# 15P2D_EDA.net
KiCad netlist of a schematic drawn in EasyEDA Pro
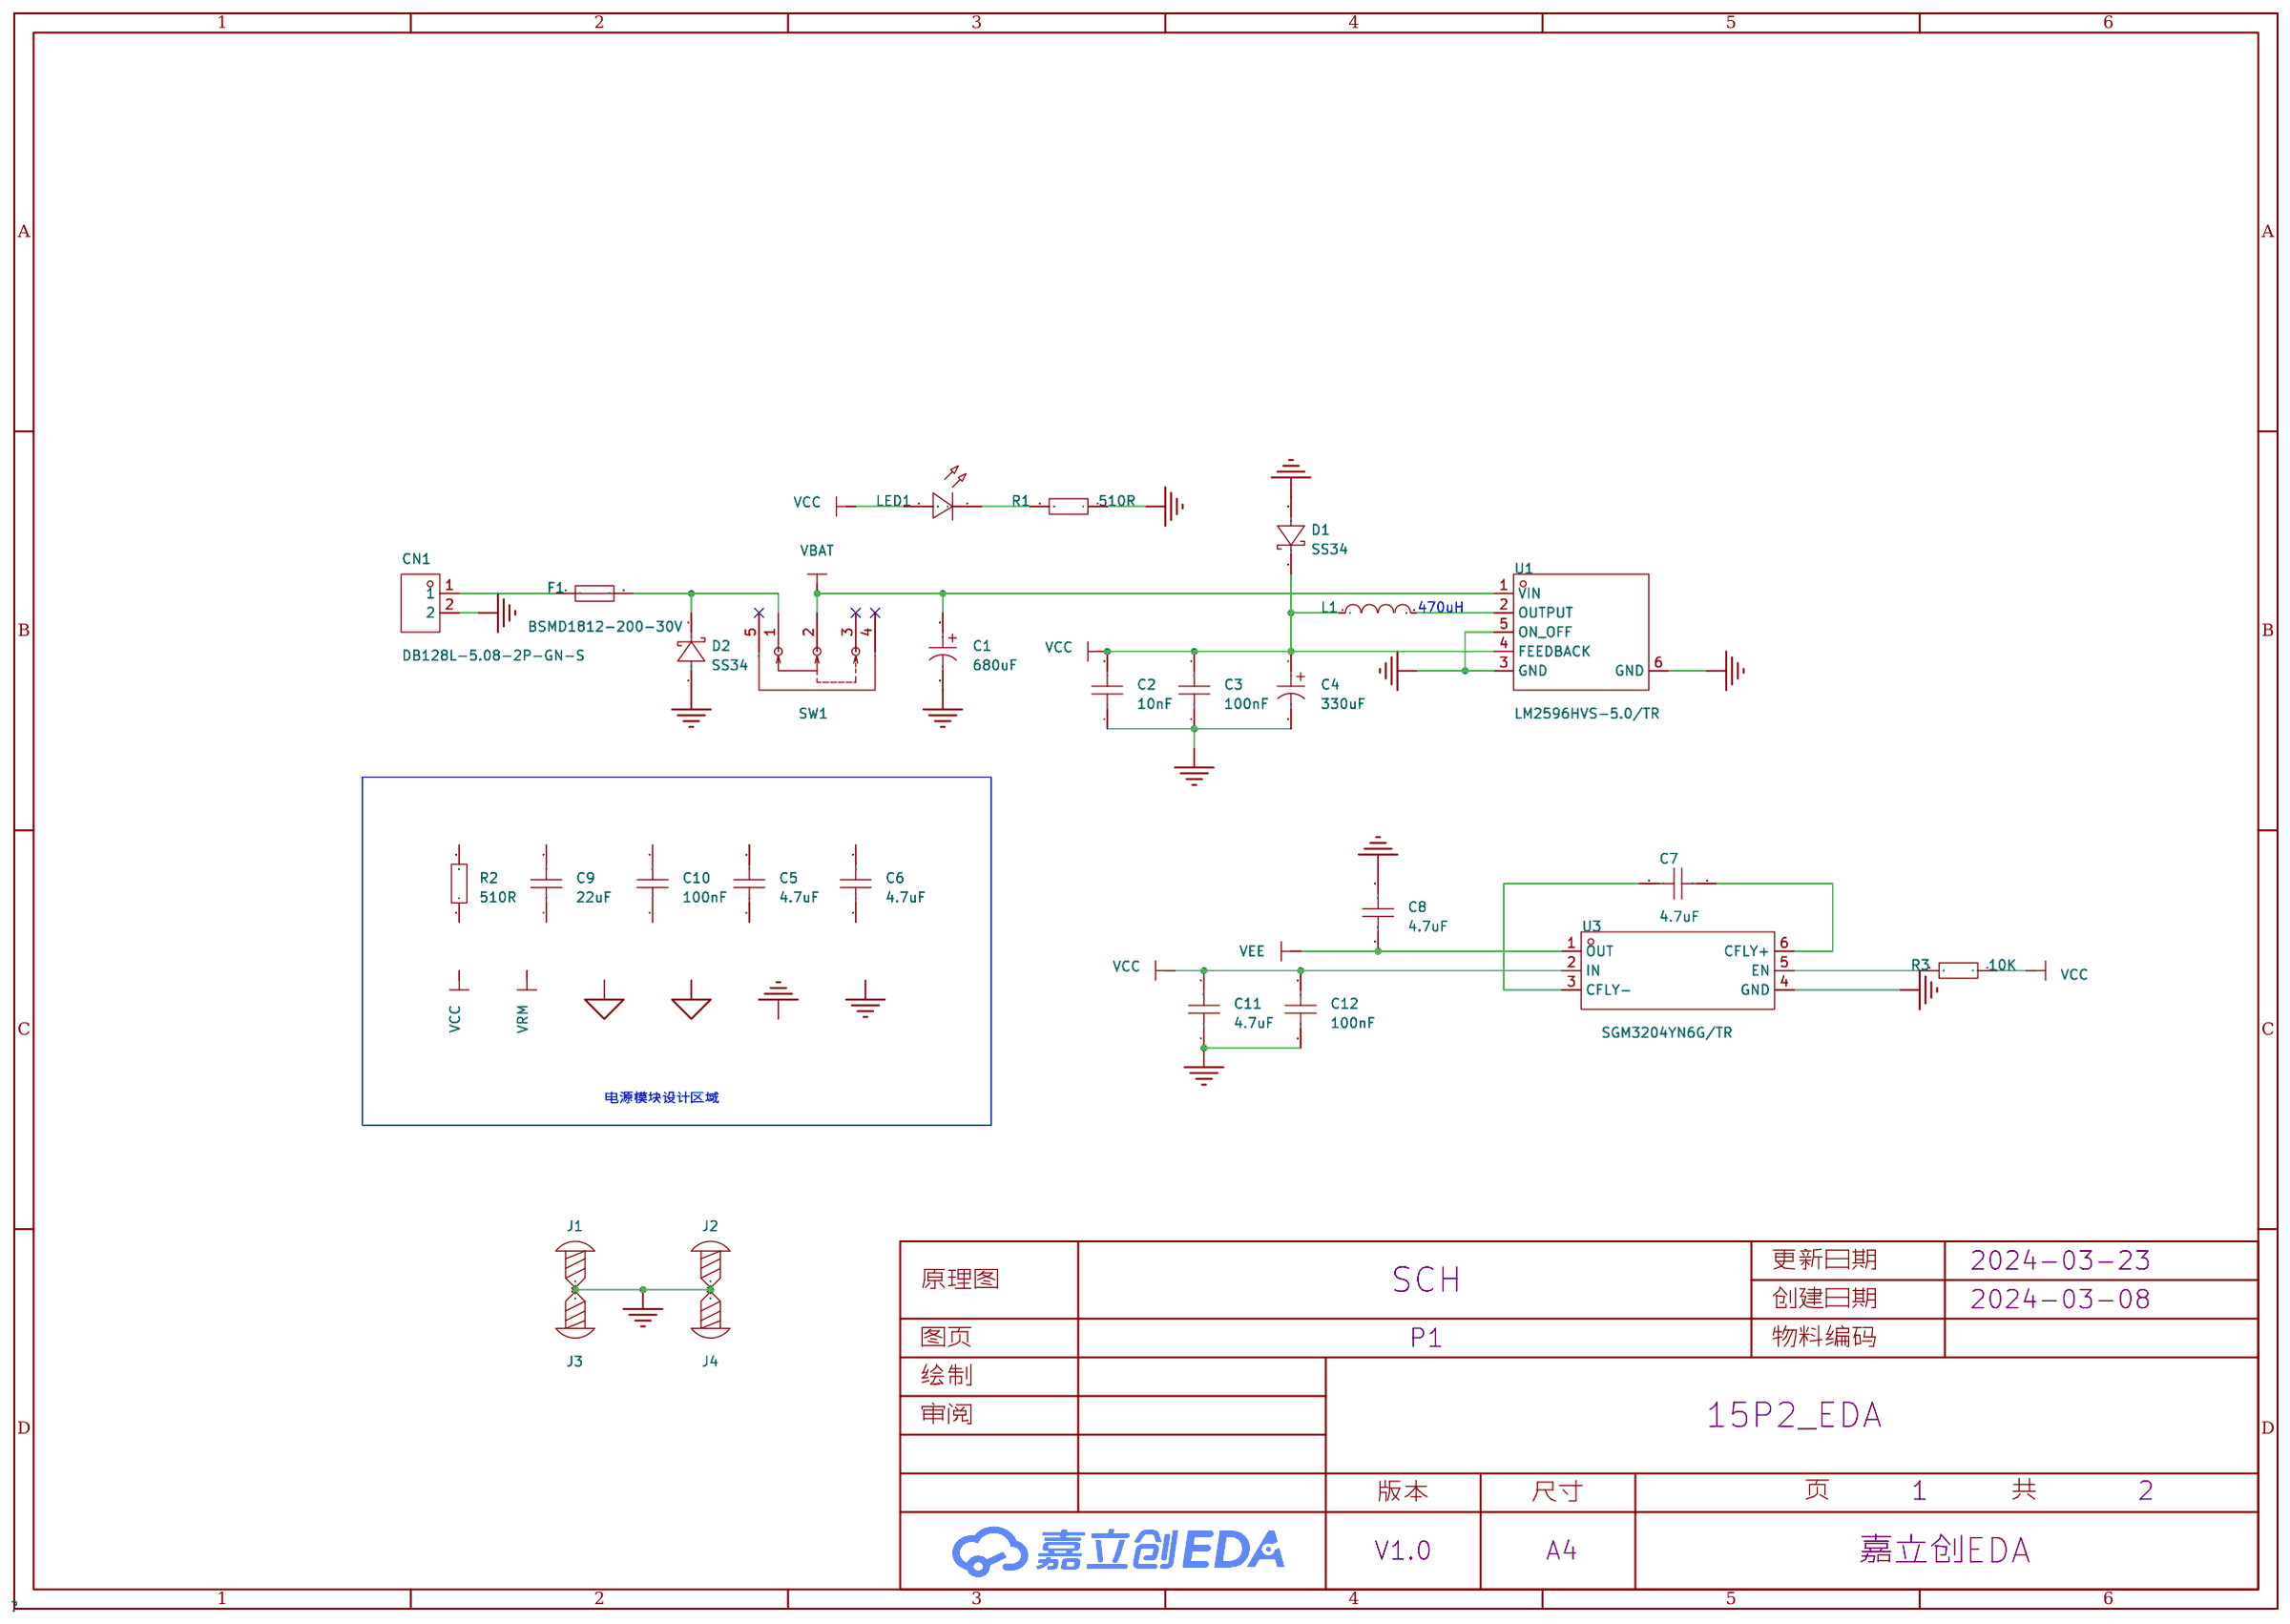
[diagram p0: P1]
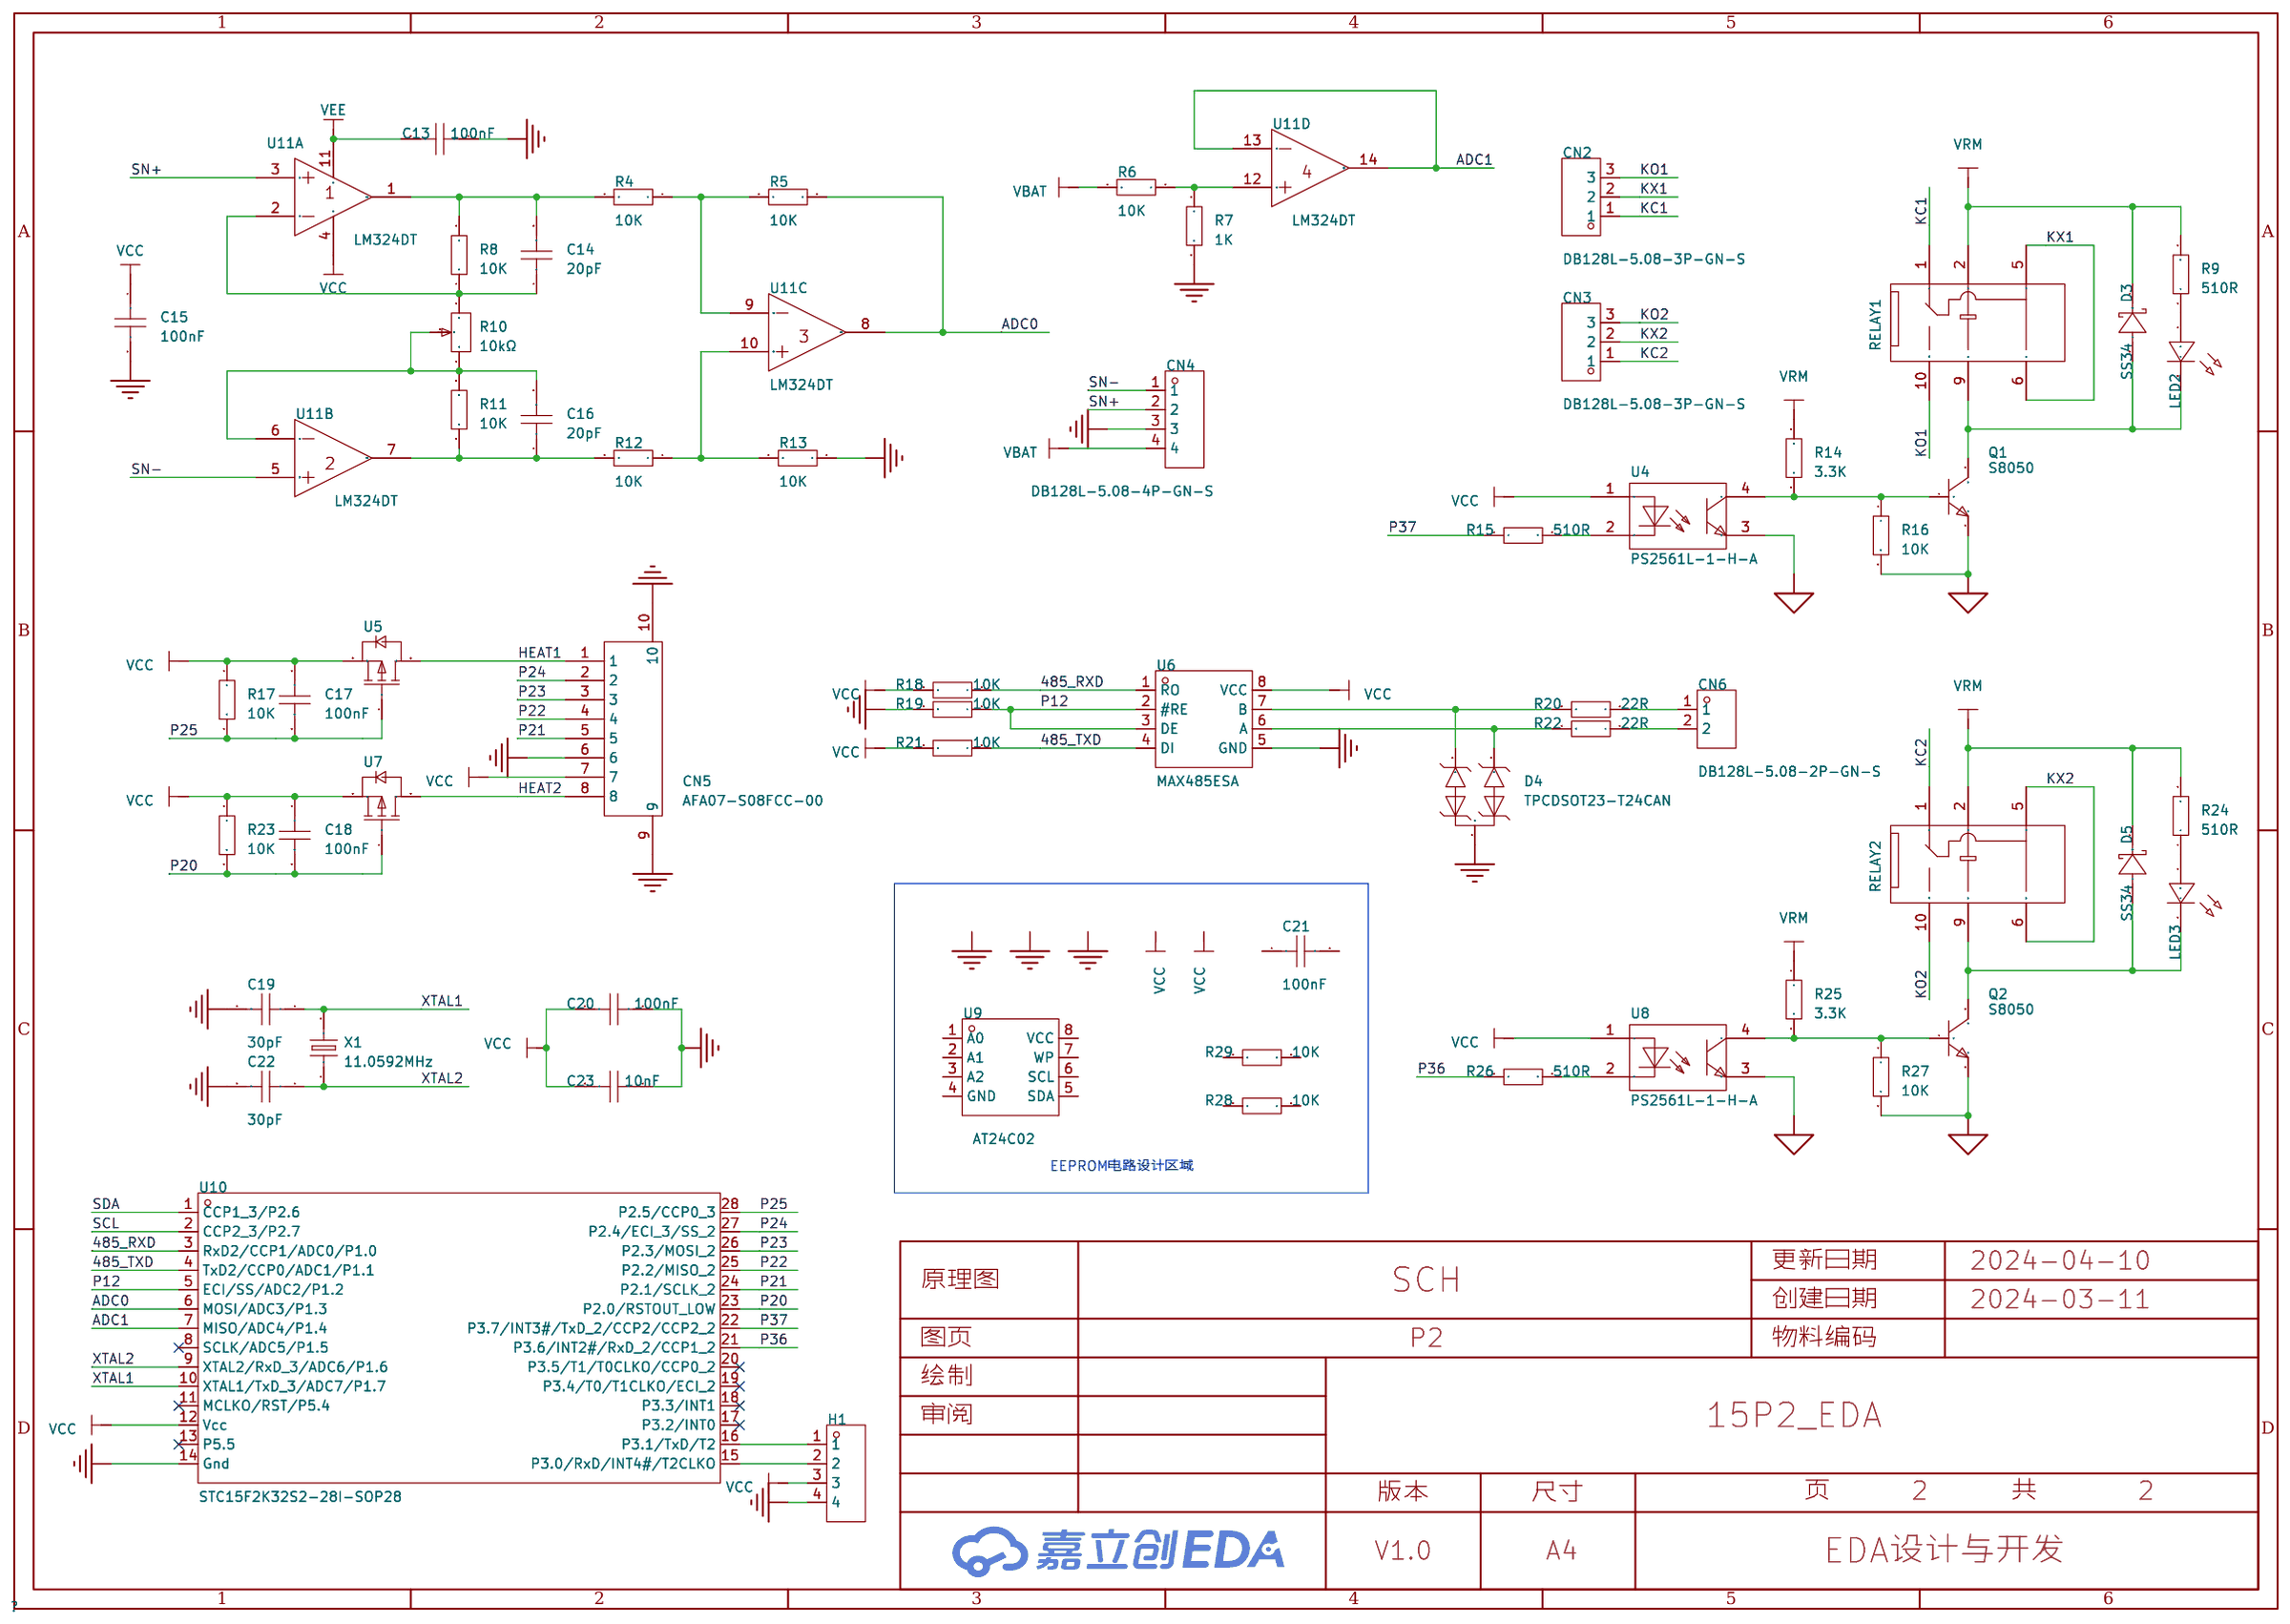
[diagram p1: P2]

(export (version "E")
  (design (tool "Eeschema 10.0.6"))
  (components
    (comp (ref "C1")
      (value "680uF")
      (footprint "easyedapro:CAP-SMD_BD10.0-L10.3-W10.3-LS11.3-FD")
      (description "容值:680uF;精度:±20%;额定电压:35V;纹波电流:380mA;")
      (fields (field (name "Manufacturer Part") "126RV0105") (field (name "Manufacturer") "KNSCHA(科尼盛)"))
      (libsource (lib "easyedapro") (part "126RV0105"))
    )
    (comp (ref "C2")
      (value "10nF")
      (footprint "easyedapro:C0805")
      (libsource (lib "easyedapro") (part "CapAcitance"))
    )
    (comp (ref "C3")
      (value "100nF")
      (footprint "easyedapro:C0805")
      (libsource (lib "easyedapro") (part "CapAcitance"))
    )
    (comp (ref "C4")
      (value "330uF")
      (footprint "easyedapro:CAP-SMD_BD6.3-L6.6-W6.6-LS7.6-RD")
      (description "容值:330uF;精度:±20%;额定电压:16V;纹波电流:170mA;")
      (fields (field (name "Manufacturer Part") "126RV0107") (field (name "Manufacturer") "KNSCHA(科尼盛)"))
      (libsource (lib "easyedapro") (part "126RV0107"))
    )
    (comp (ref "C5")
      (value "4.7uF")
      (footprint "easyedapro:C1206")
      (description "容值:22uF;精度:±10%;额定电压:16V;材质(温度系数):X5R;")
      (fields
        (field (name "Manufacturer Part") "CL31A226KOHNNNE")
        (field (name "Manufacturer") "SAMSUNG(三星)")
      )
      (libsource (lib "easyedapro") (part "CL31A226KOHNNNE"))
    )
    (comp (ref "C6")
      (value "4.7uF")
      (footprint "easyedapro:C1206")
      (description "容值:22uF;精度:±10%;额定电压:16V;材质(温度系数):X5R;")
      (fields
        (field (name "Manufacturer Part") "CL31A226KOHNNNE")
        (field (name "Manufacturer") "SAMSUNG(三星)")
      )
      (libsource (lib "easyedapro") (part "CL31A226KOHNNNE"))
    )
    (comp (ref "C7")
      (value "4.7uF")
      (footprint "easyedapro:C1206")
      (description "容值:22uF;精度:±10%;额定电压:16V;材质(温度系数):X5R;")
      (fields
        (field (name "Manufacturer Part") "CL31A226KOHNNNE")
        (field (name "Manufacturer") "SAMSUNG(三星)")
      )
      (libsource (lib "easyedapro") (part "CL31A226KOHNNNE"))
    )
    (comp (ref "C8")
      (value "4.7uF")
      (footprint "easyedapro:C1206")
      (description "容值:22uF;精度:±10%;额定电压:16V;材质(温度系数):X5R;")
      (fields
        (field (name "Manufacturer Part") "CL31A226KOHNNNE")
        (field (name "Manufacturer") "SAMSUNG(三星)")
      )
      (libsource (lib "easyedapro") (part "CL31A226KOHNNNE"))
    )
    (comp (ref "C9")
      (value "22uF")
      (footprint "easyedapro:C1206")
      (description "容值:22uF;精度:±10%;额定电压:16V;材质(温度系数):X5R;")
      (fields
        (field (name "Manufacturer Part") "CL31A226KOHNNNE")
        (field (name "Manufacturer") "SAMSUNG(三星)")
      )
      (libsource (lib "easyedapro") (part "CL31A226KOHNNNE"))
    )
    (comp (ref "C10")
      (value "100nF")
      (footprint "easyedapro:C0805")
      (libsource (lib "easyedapro") (part "CapAcitance"))
    )
    (comp (ref "C11")
      (value "4.7uF")
      (footprint "easyedapro:C1206")
      (description "容值:22uF;精度:±10%;额定电压:16V;材质(温度系数):X5R;")
      (fields
        (field (name "Manufacturer Part") "CL31A226KOHNNNE")
        (field (name "Manufacturer") "SAMSUNG(三星)")
      )
      (libsource (lib "easyedapro") (part "CL31A226KOHNNNE"))
    )
    (comp (ref "C12")
      (value "100nF")
      (footprint "easyedapro:C0805")
      (libsource (lib "easyedapro") (part "CapAcitance"))
    )
    (comp (ref "CN1")
      (value "DB128L-5.08-2P-GN-S")
      (footprint "easyedapro:CONN-TH_2P-P5.08_DB128L-5.08-2P")
      (fields (field (name "Manufacturer") "DORABO(地博电气)"))
      (libsource (lib "easyedapro") (part "DB128L-5.08-2P"))
    )
    (comp (ref "D1")
      (value "SS34")
      (footprint "easyedapro:SMA_L4.3-W2.5-LS5.0-RD")
      (description "二极管配置:独立式;正向压降(Vf):550mV@3A;直流反向耐压(Vr):40V;平均整流电流(Io):3A;")
      (fields (field (name "Manufacturer") "TWGMC(台湾迪嘉)"))
      (libsource (lib "easyedapro") (part "SS34_C727060"))
    )
    (comp (ref "D2")
      (value "SS34")
      (footprint "easyedapro:SMA_L4.3-W2.5-LS5.0-RD")
      (description "二极管配置:独立式;正向压降(Vf):550mV@3A;直流反向耐压(Vr):40V;平均整流电流(Io):3A;")
      (fields (field (name "Manufacturer") "TWGMC(台湾迪嘉)"))
      (libsource (lib "easyedapro") (part "SS34_C727060"))
    )
    (comp (ref "F1")
      (value "BSMD1812-200-30V")
      (footprint "easyedapro:F1812")
      (description "最大电压:30V;最大电流:40A;保持电流:2A;跳闸电流:4A;")
      (fields (field (name "Manufacturer") "BHFUSE(佰宏)"))
      (libsource (lib "easyedapro") (part "BSMD1812-200-30V"))
    )
    (comp (ref "J1") (value "~") (footprint "easyedapro:M2螺丝") (libsource (lib "easyedapro") (part "螺丝孔")))
    (comp (ref "J2") (value "~") (footprint "easyedapro:M2螺丝") (libsource (lib "easyedapro") (part "螺丝孔")))
    (comp (ref "J3") (value "~") (footprint "easyedapro:M2螺丝") (libsource (lib "easyedapro") (part "螺丝孔")))
    (comp (ref "J4") (value "~") (footprint "easyedapro:M2螺丝") (libsource (lib "easyedapro") (part "螺丝孔")))
    (comp (ref "L1")
      (value "470uH")
      (footprint "easyedapro:IND-SMD_L12.0-W12.0_YPRH120X")
      (description "电感值:470uH;精度:±20%;额定电流:1.06A;")
      (fields (field (name "Manufacturer Part") "YPRH1209-471M") (field (name "Manufacturer") "YJYCOIN(益嘉源)"))
      (libsource (lib "easyedapro") (part "YPRH1209-471M"))
    )
    (comp (ref "LED1")
      (value "~")
      (footprint "easyedapro:LED_TH-3mm")
      (libsource (lib "easyedapro") (part "LED_TH-R"))
    )
    (comp (ref "R1") (value "510R") (footprint "easyedapro:R0805") (libsource (lib "easyedapro") (part "电阻")))
    (comp (ref "R2") (value "510R") (footprint "easyedapro:R0805") (libsource (lib "easyedapro") (part "电阻")))
    (comp (ref "R3") (value "10K") (footprint "easyedapro:R0805") (libsource (lib "easyedapro") (part "电阻")))
    (comp (ref "SW1")
      (value "SK12D07VG4")
      (footprint "easyedapro:SW-TH_SK12D07VG4")
      (description "电路结构:单刀双掷;安装方式:侧插;额定电流(DC):500mA;额定电压(DC):50V;额定电流(AC):-;额定电压(AC):-;机械寿命:5千次;")
      (fields (field (name "Manufacturer") "SHOU HAN(首韩)"))
      (libsource (lib "easyedapro") (part "SK12D07VG4"))
    )
    (comp (ref "U1")
      (value "LM2596HVS-5.0/TR")
      (footprint "easyedapro:TO-263-5_L10.2-W8.9-P1.70-LS15.2-BR")
      (fields (field (name "Manufacturer") "HGSEMI(华冠)"))
      (libsource (lib "easyedapro") (part "LM2596HVS-5.0/TR"))
    )
    (comp (ref "U3")
      (value "SGM3204YN6G/TR")
      (footprint "easyedapro:SOT-23-6_L2.9-W1.6-P0.95-LS2.8-BR")
      (description "功能类型:-;输入电压:1.4V~5.5V;输出电压:-5.5V~-1.4V;输出电流(最大值):200mA;")
      (fields (field (name "Manufacturer") "SGMICRO(圣邦微)"))
      (libsource (lib "easyedapro") (part "SGM3204YN6G/TR"))
    )
    (comp (ref "C13")
      (value "100nF")
      (footprint "easyedapro:C0805")
      (libsource (lib "easyedapro") (part "CapAcitance"))
    )
    (comp (ref "C14")
      (value "20pF")
      (footprint "easyedapro:C0805")
      (libsource (lib "easyedapro") (part "CapAcitance"))
    )
    (comp (ref "C15")
      (value "100nF")
      (footprint "easyedapro:C0805")
      (libsource (lib "easyedapro") (part "CapAcitance"))
    )
    (comp (ref "C16")
      (value "20pF")
      (footprint "easyedapro:C0805")
      (libsource (lib "easyedapro") (part "CapAcitance"))
    )
    (comp (ref "C17")
      (value "100nF")
      (footprint "easyedapro:C0805")
      (libsource (lib "easyedapro") (part "CapAcitance"))
    )
    (comp (ref "C18")
      (value "100nF")
      (footprint "easyedapro:C0805")
      (libsource (lib "easyedapro") (part "CapAcitance"))
    )
    (comp (ref "C19")
      (value "30pF")
      (footprint "easyedapro:C0805")
      (libsource (lib "easyedapro") (part "CapAcitance"))
    )
    (comp (ref "C20")
      (value "100nF")
      (footprint "easyedapro:C0805")
      (libsource (lib "easyedapro") (part "CapAcitance"))
    )
    (comp (ref "C21")
      (value "100nF")
      (footprint "easyedapro:C0805")
      (libsource (lib "easyedapro") (part "CapAcitance"))
    )
    (comp (ref "C22")
      (value "30pF")
      (footprint "easyedapro:C0805")
      (libsource (lib "easyedapro") (part "CapAcitance"))
    )
    (comp (ref "C23")
      (value "10nF")
      (footprint "easyedapro:C0805")
      (libsource (lib "easyedapro") (part "CapAcitance"))
    )
    (comp (ref "CN2")
      (value "DB128L-5.08-3P-GN-S")
      (footprint "easyedapro:CONN-TH_DB128L-5.08-3P")
      (fields (field (name "Manufacturer") "DORABO(地博电气)"))
      (libsource (lib "easyedapro") (part "DB128L-5.08-3P"))
    )
    (comp (ref "CN3")
      (value "DB128L-5.08-3P-GN-S")
      (footprint "easyedapro:CONN-TH_DB128L-5.08-3P")
      (fields (field (name "Manufacturer") "DORABO(地博电气)"))
      (libsource (lib "easyedapro") (part "DB128L-5.08-3P"))
    )
    (comp (ref "CN4")
      (value "DB128L-5.08-4P-GN-S")
      (footprint "easyedapro:CONN-TH_4P_DB128L-5.08-4P-GN-S")
      (fields (field (name "Manufacturer") "DORABO(地博电气)"))
      (libsource (lib "easyedapro") (part "DB128L-5.08-4P-GN-S"))
    )
    (comp (ref "CN5")
      (value "AFA07-S08FCC-00")
      (footprint "easyedapro:FPC-SMD_P1.00-8P_LCS-XJ-H2.5")
      (description "锁定特性:抽屉式;触点类型:下接;触点数量:8P;间距:1mm;安装类型:卧贴;")
      (fields (field (name "Manufacturer") "JS(钜硕电子)"))
      (libsource (lib "easyedapro") (part "AFA07-S08FCC-00"))
    )
    (comp (ref "CN6")
      (value "DB128L-5.08-2P-GN-S")
      (footprint "easyedapro:CONN-TH_2P-P5.08_DB128L-5.08-2P")
      (fields (field (name "Manufacturer") "DORABO(地博电气)"))
      (libsource (lib "easyedapro") (part "DB128L-5.08-2P"))
    )
    (comp (ref "D3")
      (value "SS34")
      (footprint "easyedapro:SMA_L4.3-W2.5-LS5.0-RD")
      (description "二极管配置:独立式;正向压降(Vf):550mV@3A;直流反向耐压(Vr):40V;平均整流电流(Io):3A;")
      (fields (field (name "Manufacturer") "TWGMC(台湾迪嘉)"))
      (libsource (lib "easyedapro") (part "SS34_C727060"))
    )
    (comp (ref "D4")
      (value "TPCDSOT23-T24CAN")
      (footprint "easyedapro:SOT-23-3_L2.9-W1.3-P1.90-LS2.4-BR")
      (fields (field (name "Manufacturer") "TECH PUBLIC(台舟)"))
      (libsource (lib "easyedapro") (part "TPCDSOT23-T24CAN"))
    )
    (comp (ref "D5")
      (value "SS34")
      (footprint "easyedapro:SMA_L4.3-W2.5-LS5.0-RD")
      (description "二极管配置:独立式;正向压降(Vf):550mV@3A;直流反向耐压(Vr):40V;平均整流电流(Io):3A;")
      (fields (field (name "Manufacturer") "TWGMC(台湾迪嘉)"))
      (libsource (lib "easyedapro") (part "SS34_C727060"))
    )
    (comp (ref "H1")
      (value "~")
      (footprint "easyedapro:HDR-TH_4P-P2.54-V-F")
      (libsource (lib "easyedapro") (part "2.54-1*4P母"))
    )
    (comp (ref "LED2")
      (value "~")
      (footprint "easyedapro:LED_TH-3mm")
      (libsource (lib "easyedapro") (part "LED_TH-G"))
    )
    (comp (ref "LED3")
      (value "~")
      (footprint "easyedapro:LED_TH-3mm")
      (libsource (lib "easyedapro") (part "LED_TH-G"))
    )
    (comp (ref "Q1")
      (value "S8050")
      (footprint "easyedapro:SOT-23-3_L2.9-W1.3-P1.90-LS2.4-BR")
      (description "晶体管类型:NPN;集电极电流(Ic):500mA;集射极击穿电压(Vceo):25V;功率(Pd):300mW;")
      (fields (field (name "Manufacturer") "YONGYUTAI(永裕泰)"))
      (libsource (lib "easyedapro") (part "S8050_C2891804"))
    )
    (comp (ref "Q2")
      (value "S8050")
      (footprint "easyedapro:SOT-23-3_L2.9-W1.3-P1.90-LS2.4-BR")
      (description "晶体管类型:NPN;集电极电流(Ic):500mA;集射极击穿电压(Vceo):25V;功率(Pd):300mW;")
      (fields (field (name "Manufacturer") "YONGYUTAI(永裕泰)"))
      (libsource (lib "easyedapro") (part "S8050_C2891804"))
    )
    (comp (ref "R4") (value "10K") (footprint "easyedapro:R0805") (libsource (lib "easyedapro") (part "电阻")))
    (comp (ref "R5") (value "10K") (footprint "easyedapro:R0805") (libsource (lib "easyedapro") (part "电阻")))
    (comp (ref "R6") (value "10K") (footprint "easyedapro:R0805") (libsource (lib "easyedapro") (part "电阻")))
    (comp (ref "R7") (value "1K") (footprint "easyedapro:R0805") (libsource (lib "easyedapro") (part "电阻")))
    (comp (ref "R8") (value "10K") (footprint "easyedapro:R0805") (libsource (lib "easyedapro") (part "电阻")))
    (comp (ref "R9") (value "510R") (footprint "easyedapro:R0805") (libsource (lib "easyedapro") (part "电阻")))
    (comp (ref "R10")
      (value "10kΩ")
      (footprint "easyedapro:RES-ADJ-TH_3P-L10.0-W10.0-P2.50-BL-BS")
      (description "阻值:20kΩ;精度:±10%;功率:500mW;温度系数:±100ppm/°C;")
      (fields (field (name "Manufacturer Part") "3296W-1-203LF") (field (name "Manufacturer") "BOURNS"))
      (libsource (lib "easyedapro") (part "3296W-1-203LF"))
    )
    (comp (ref "R11") (value "10K") (footprint "easyedapro:R0805") (libsource (lib "easyedapro") (part "电阻")))
    (comp (ref "R12") (value "10K") (footprint "easyedapro:R0805") (libsource (lib "easyedapro") (part "电阻")))
    (comp (ref "R13") (value "10K") (footprint "easyedapro:R0805") (libsource (lib "easyedapro") (part "电阻")))
    (comp (ref "R14")
      (value "3.3K")
      (footprint "easyedapro:R0805")
      (libsource (lib "easyedapro") (part "电阻"))
    )
    (comp (ref "R15")
      (value "510R")
      (footprint "easyedapro:R0805")
      (libsource (lib "easyedapro") (part "电阻"))
    )
    (comp (ref "R16") (value "10K") (footprint "easyedapro:R0805") (libsource (lib "easyedapro") (part "电阻")))
    (comp (ref "R17") (value "10K") (footprint "easyedapro:R0805") (libsource (lib "easyedapro") (part "电阻")))
    (comp (ref "R18") (value "10K") (footprint "easyedapro:R0805") (libsource (lib "easyedapro") (part "电阻")))
    (comp (ref "R19") (value "10K") (footprint "easyedapro:R0805") (libsource (lib "easyedapro") (part "电阻")))
    (comp (ref "R20") (value "22R") (footprint "easyedapro:R0805") (libsource (lib "easyedapro") (part "电阻")))
    (comp (ref "R21") (value "10K") (footprint "easyedapro:R0805") (libsource (lib "easyedapro") (part "电阻")))
    (comp (ref "R22") (value "22R") (footprint "easyedapro:R0805") (libsource (lib "easyedapro") (part "电阻")))
    (comp (ref "R23") (value "10K") (footprint "easyedapro:R0805") (libsource (lib "easyedapro") (part "电阻")))
    (comp (ref "R24")
      (value "510R")
      (footprint "easyedapro:R0805")
      (libsource (lib "easyedapro") (part "电阻"))
    )
    (comp (ref "R25")
      (value "3.3K")
      (footprint "easyedapro:R0805")
      (libsource (lib "easyedapro") (part "电阻"))
    )
    (comp (ref "R26")
      (value "510R")
      (footprint "easyedapro:R0805")
      (libsource (lib "easyedapro") (part "电阻"))
    )
    (comp (ref "R27") (value "10K") (footprint "easyedapro:R0805") (libsource (lib "easyedapro") (part "电阻")))
    (comp (ref "R28") (value "10K") (footprint "easyedapro:R0805") (libsource (lib "easyedapro") (part "电阻")))
    (comp (ref "R29") (value "10K") (footprint "easyedapro:R0805") (libsource (lib "easyedapro") (part "电阻")))
    (comp (ref "RELAY1")
      (value "G5V-1 DC5")
      (footprint "easyedapro:RELAY-TH_G5V-1")
      (description "线圈电压:5V;触点形式:一组转换:1C(单刀双掷-转换);触点容量(电阻负载):-;最大切换电压:125V@AC；60V@DC;最大切换电流:1A;")
      (fields (field (name "Manufacturer") "OMRON(欧姆龙)"))
      (libsource (lib "easyedapro") (part "G5V-1-5VDC"))
    )
    (comp (ref "RELAY2")
      (value "G5V-1 DC5")
      (footprint "easyedapro:RELAY-TH_G5V-1")
      (description "线圈电压:5V;触点形式:一组转换:1C(单刀双掷-转换);触点容量(电阻负载):-;最大切换电压:125V@AC；60V@DC;最大切换电流:1A;")
      (fields (field (name "Manufacturer") "OMRON(欧姆龙)"))
      (libsource (lib "easyedapro") (part "G5V-1-5VDC"))
    )
    (comp (ref "U4")
      (value "PS2561L-1-H-A")
      (footprint "easyedapro:SOP-4_L6.5-W4.6-P2.54-LS9.6-TL")
      (fields (field (name "Manufacturer") "California Eastern Laboratories"))
      (libsource (lib "easyedapro") (part "PS2561L-1-H-A"))
    )
    (comp (ref "U5")
      (value "SI2301-ZE")
      (footprint "easyedapro:SOT-23-3_L2.9-W1.3-P1.90-LS2.4-BR")
      (fields (field (name "Manufacturer") "HXY MOSFET(华轩阳电子)"))
      (libsource (lib "easyedapro") (part "SI2301-ZE"))
    )
    (comp (ref "U6")
      (value "MAX485ESA")
      (footprint "easyedapro:SOP-8_L5.0-W4.0-P1.27-LS6.0-BL")
      (fields (field (name "Manufacturer") "UMW(友台半导体)"))
      (libsource (lib "easyedapro") (part "MAX485EAS"))
    )
    (comp (ref "U7")
      (value "SI2301-ZE")
      (footprint "easyedapro:SOT-23-3_L2.9-W1.3-P1.90-LS2.4-BR")
      (fields (field (name "Manufacturer") "HXY MOSFET(华轩阳电子)"))
      (libsource (lib "easyedapro") (part "SI2301-ZE"))
    )
    (comp (ref "U8")
      (value "PS2561L-1-H-A")
      (footprint "easyedapro:SOP-4_L6.5-W4.6-P2.54-LS9.6-TL")
      (fields (field (name "Manufacturer") "California Eastern Laboratories"))
      (libsource (lib "easyedapro") (part "PS2561L-1-H-A"))
    )
    (comp (ref "U9")
      (value "AT24C02")
      (footprint "easyedapro:SOP-8_L4.9-W3.9-P1.27-LS6.0-BL")
      (description "接口类型:I2C;存储容量:2Kbit;时钟频率(fc):400kHz~1MHz;")
      (fields (field (name "Manufacturer") "HXY MOSFET(华轩阳电子)"))
      (libsource (lib "easyedapro") (part "AT24C02_C7470930"))
    )
    (comp (ref "U10")
      (value "STC15F2K32S2-28I-SOP28")
      (footprint "easyedapro:SOP-28_L17.9-W7.5-P1.27-LS10.3-BL")
      (fields (field (name "Manufacturer") "STC(宏晶)"))
      (libsource (lib "easyedapro") (part "STC15F2K32S2-28I-SOP28"))
    )
    (comp (ref "U11")
      (value "LM324DT")
      (footprint "easyedapro:SOIC-14_L8.7-W3.9-P1.27-LS6.0-BL")
      (description "放大器数:四路;增益带宽积(GBP):1.3MHz;输入偏置电流(Ib):20nA;压摆率(SR):0.4V/us;带宽(-3db):-;")
      (fields (field (name "Manufacturer") "ST(意法半导体)"))
      (libsource (lib "easyedapro") (part "LM324DT"))
    )
    (comp (ref "X1")
      (value "11.0592MHz")
      (footprint "easyedapro:HC-49US_L11.5-W4.5-P4.88")
      (description "晶振类型:直插晶振;频率:11.0592MHz;常温频差:±30ppm;外接负载电容:20pF;频率稳定度(全温):±30ppm;")
      (fields
        (field (name "Manufacturer Part") "TAXD11.0592M2GLFBET2T")
        (field (name "Manufacturer") "YJX(雅晶鑫)")
      )
      (libsource (lib "easyedapro") (part "HC-49S11.0592MHZ20PF30PPM"))
    )
  )
  (nets
    (net (code "1") (name "0") (class "Default")
      (node (ref "Q1") (pin "2") (pinfunction "E_2") (pintype "unspecified"))
      (node (ref "Q2") (pin "2") (pinfunction "E_2") (pintype "unspecified"))
      (node (ref "R16") (pin "2") (pinfunction "2_2") (pintype "input"))
      (node (ref "R27") (pin "2") (pinfunction "2_2") (pintype "input"))
      (node (ref "U4") (pin "3") (pinfunction "3_3") (pintype "input"))
      (node (ref "U8") (pin "3") (pinfunction "3_3") (pintype "input"))
    )
    (net (code "2") (name "485_RXD") (class "Default")
      (node (ref "R18") (pin "1") (pinfunction "1_1") (pintype "input"))
      (node (ref "U10") (pin "3") (pinfunction "RxD2/CCP1/ADC0/P1.0_3") (pintype "input"))
      (node (ref "U6") (pin "1") (pinfunction "RO_1") (pintype "unspecified"))
    )
    (net (code "3") (name "485_TXD") (class "Default")
      (node (ref "R21") (pin "1") (pinfunction "1_1") (pintype "input"))
      (node (ref "U10") (pin "4") (pinfunction "TxD2/CCP0/ADC1/P1.1_4") (pintype "input"))
      (node (ref "U6") (pin "4") (pinfunction "DI_4") (pintype "unspecified"))
    )
    (net (code "4") (name "ADC0") (class "Default")
      (node (ref "R5") (pin "1") (pinfunction "1_1") (pintype "input"))
      (node (ref "U10") (pin "6") (pinfunction "MOSI/ADC3/P1.3_6") (pintype "input"))
      (node (ref "U11") (pin "8") (pinfunction "OUT3_8") (pintype "unspecified"))
    )
    (net (code "5") (name "ADC1") (class "Default")
      (node (ref "U10") (pin "7") (pinfunction "MISO/ADC4/P1.4_7") (pintype "input"))
      (node (ref "U11") (pin "13") (pinfunction "IN4-_13") (pintype "unspecified"))
      (node (ref "U11") (pin "14") (pinfunction "OUT4_14") (pintype "unspecified"))
    )
    (net (code "6") (name "GND") (class "Default")
      (node (ref "C1") (pin "2") (pinfunction "2_2") (pintype "input"))
      (node (ref "C11") (pin "1") (pinfunction "1_1") (pintype "unspecified"))
      (node (ref "C12") (pin "1") (pinfunction "1_1") (pintype "input"))
      (node (ref "C13") (pin "1") (pinfunction "1_1") (pintype "input"))
      (node (ref "C15") (pin "2") (pinfunction "2_2") (pintype "input"))
      (node (ref "C19") (pin "2") (pinfunction "2_2") (pintype "input"))
      (node (ref "C2") (pin "1") (pinfunction "1_1") (pintype "input"))
      (node (ref "C20") (pin "1") (pinfunction "1_1") (pintype "input"))
      (node (ref "C22") (pin "2") (pinfunction "2_2") (pintype "input"))
      (node (ref "C23") (pin "1") (pinfunction "1_1") (pintype "input"))
      (node (ref "C3") (pin "1") (pinfunction "1_1") (pintype "input"))
      (node (ref "C4") (pin "2") (pinfunction "2_2") (pintype "input"))
      (node (ref "C8") (pin "1") (pinfunction "1_1") (pintype "unspecified"))
      (node (ref "CN1") (pin "2") (pinfunction "2_2") (pintype "unspecified"))
      (node (ref "CN4") (pin "3") (pinfunction "3_3") (pintype "unspecified"))
      (node (ref "CN5") (pin "10") (pinfunction "10_10") (pintype "unspecified"))
      (node (ref "CN5") (pin "6") (pinfunction "6_6") (pintype "unspecified"))
      (node (ref "CN5") (pin "9") (pinfunction "9_9") (pintype "unspecified"))
      (node (ref "D1") (pin "2") (pinfunction "A_2") (pintype "unspecified"))
      (node (ref "D2") (pin "2") (pinfunction "A_2") (pintype "unspecified"))
      (node (ref "D4") (pin "3") (pinfunction "3_3") (pintype "unspecified"))
      (node (ref "H1") (pin "4") (pinfunction "4_4") (pintype "unspecified"))
      (node (ref "J1") (pin "1") (pinfunction "1_1") (pintype "input"))
      (node (ref "J2") (pin "1") (pinfunction "1_1") (pintype "input"))
      (node (ref "J3") (pin "1") (pinfunction "1_1") (pintype "input"))
      (node (ref "J4") (pin "1") (pinfunction "1_1") (pintype "input"))
      (node (ref "R1") (pin "1") (pinfunction "1_1") (pintype "input"))
      (node (ref "R13") (pin "1") (pinfunction "1_1") (pintype "input"))
      (node (ref "R19") (pin "2") (pinfunction "2_2") (pintype "input"))
      (node (ref "R7") (pin "2") (pinfunction "2_2") (pintype "input"))
      (node (ref "U1") (pin "3") (pinfunction "GND_3") (pintype "input"))
      (node (ref "U1") (pin "5") (pinfunction "ON_OFF_5") (pintype "input"))
      (node (ref "U1") (pin "6") (pinfunction "GND_6") (pintype "input"))
      (node (ref "U10") (pin "14") (pinfunction "Gnd_14") (pintype "input"))
      (node (ref "U3") (pin "4") (pinfunction "GND_4") (pintype "unspecified"))
      (node (ref "U6") (pin "5") (pinfunction "GND_5") (pintype "unspecified"))
    )
    (net (code "7") (name "HEAT1") (class "Default")
      (node (ref "CN5") (pin "1") (pinfunction "1_1") (pintype "unspecified"))
      (node (ref "U5") (pin "3") (pinfunction "D_3") (pintype "unspecified"))
    )
    (net (code "8") (name "HEAT2") (class "Default")
      (node (ref "CN5") (pin "8") (pinfunction "8_8") (pintype "unspecified"))
      (node (ref "U7") (pin "3") (pinfunction "D_3") (pintype "unspecified"))
    )
    (net (code "9") (name "KC1") (class "Default")
      (node (ref "CN2") (pin "1") (pinfunction "1_1") (pintype "unspecified"))
      (node (ref "RELAY1") (pin "1") (pinfunction "1_1") (pintype "input"))
    )
    (net (code "10") (name "KC2") (class "Default")
      (node (ref "CN3") (pin "1") (pinfunction "1_1") (pintype "unspecified"))
      (node (ref "RELAY2") (pin "1") (pinfunction "1_1") (pintype "input"))
    )
    (net (code "11") (name "KO1") (class "Default")
      (node (ref "CN2") (pin "3") (pinfunction "3_3") (pintype "unspecified"))
      (node (ref "RELAY1") (pin "10") (pinfunction "10_10") (pintype "input"))
    )
    (net (code "12") (name "KO2") (class "Default")
      (node (ref "CN3") (pin "3") (pinfunction "3_3") (pintype "unspecified"))
      (node (ref "RELAY2") (pin "10") (pinfunction "10_10") (pintype "input"))
    )
    (net (code "13") (name "KX1") (class "Default")
      (node (ref "CN2") (pin "2") (pinfunction "2_2") (pintype "unspecified"))
      (node (ref "RELAY1") (pin "5") (pinfunction "5_5") (pintype "input"))
      (node (ref "RELAY1") (pin "6") (pinfunction "6_6") (pintype "input"))
    )
    (net (code "14") (name "KX2") (class "Default")
      (node (ref "CN3") (pin "2") (pinfunction "2_2") (pintype "unspecified"))
      (node (ref "RELAY2") (pin "5") (pinfunction "5_5") (pintype "input"))
      (node (ref "RELAY2") (pin "6") (pinfunction "6_6") (pintype "input"))
    )
    (net (code "15") (name "Net-(CN1-Pad1)") (class "Default")
      (node (ref "CN1") (pin "1") (pinfunction "1_1") (pintype "unspecified"))
      (node (ref "F1") (pin "1") (pinfunction "1_1") (pintype "unspecified"))
    )
    (net (code "16") (name "Net-(CN6-Pad1)") (class "Default")
      (node (ref "CN6") (pin "1") (pinfunction "1_1") (pintype "unspecified"))
      (node (ref "R20") (pin "1") (pinfunction "1_1") (pintype "input"))
    )
    (net (code "17") (name "Net-(CN6-Pad2)") (class "Default")
      (node (ref "CN6") (pin "2") (pinfunction "2_2") (pintype "unspecified"))
      (node (ref "R22") (pin "1") (pinfunction "1_1") (pintype "input"))
    )
    (net (code "18") (name "Net-(D2-C)") (class "Default")
      (node (ref "D2") (pin "1") (pinfunction "C_1") (pintype "unspecified"))
      (node (ref "F1") (pin "2") (pinfunction "2_2") (pintype "unspecified"))
      (node (ref "SW1") (pin "1") (pinfunction "1_1") (pintype "unspecified"))
    )
    (net (code "19") (name "Net-(D3-A)") (class "Default")
      (node (ref "D3") (pin "2") (pinfunction "A_2") (pintype "unspecified"))
      (node (ref "LED2") (pin "2") (pinfunction "A_2") (pintype "input"))
      (node (ref "Q1") (pin "3") (pinfunction "C_3") (pintype "unspecified"))
      (node (ref "RELAY1") (pin "9") (pinfunction "9_9") (pintype "input"))
    )
    (net (code "20") (name "Net-(D5-A)") (class "Default")
      (node (ref "D5") (pin "2") (pinfunction "A_2") (pintype "unspecified"))
      (node (ref "LED3") (pin "2") (pinfunction "A_2") (pintype "input"))
      (node (ref "Q2") (pin "3") (pinfunction "C_3") (pintype "unspecified"))
      (node (ref "RELAY2") (pin "9") (pinfunction "9_9") (pintype "input"))
    )
    (net (code "21") (name "Net-(LED1-A)") (class "Default")
      (node (ref "LED1") (pin "2") (pinfunction "A_2") (pintype "input"))
      (node (ref "R1") (pin "2") (pinfunction "2_2") (pintype "input"))
    )
    (net (code "22") (name "Net-(LED2-C)") (class "Default")
      (node (ref "LED2") (pin "1") (pinfunction "C_1") (pintype "input"))
      (node (ref "R9") (pin "1") (pinfunction "1_1") (pintype "input"))
    )
    (net (code "23") (name "Net-(LED3-C)") (class "Default")
      (node (ref "LED3") (pin "1") (pinfunction "C_1") (pintype "input"))
      (node (ref "R24") (pin "1") (pinfunction "1_1") (pintype "input"))
    )
    (net (code "24") (name "Net-(Q1-B)") (class "Default")
      (node (ref "Q1") (pin "1") (pinfunction "B_1") (pintype "unspecified"))
      (node (ref "R14") (pin "2") (pinfunction "2_2") (pintype "input"))
      (node (ref "R16") (pin "1") (pinfunction "1_1") (pintype "input"))
      (node (ref "U4") (pin "4") (pinfunction "4_4") (pintype "input"))
    )
    (net (code "25") (name "Net-(Q2-B)") (class "Default")
      (node (ref "Q2") (pin "1") (pinfunction "B_1") (pintype "unspecified"))
      (node (ref "R25") (pin "2") (pinfunction "2_2") (pintype "input"))
      (node (ref "R27") (pin "1") (pinfunction "1_1") (pintype "input"))
      (node (ref "U8") (pin "4") (pinfunction "4_4") (pintype "input"))
    )
    (net (code "26") (name "Net-(R15-Pad2)") (class "Default")
      (node (ref "R15") (pin "2") (pinfunction "2_2") (pintype "input"))
      (node (ref "U4") (pin "2") (pinfunction "2_2") (pintype "input"))
    )
    (net (code "27") (name "Net-(R26-Pad2)") (class "Default")
      (node (ref "R26") (pin "2") (pinfunction "2_2") (pintype "input"))
      (node (ref "U8") (pin "2") (pinfunction "2_2") (pintype "input"))
    )
    (net (code "28") (name "Net-(U1-OUTPUT)") (class "Default")
      (node (ref "L1") (pin "2") (pinfunction "2_2") (pintype "unspecified"))
      (node (ref "U1") (pin "2") (pinfunction "OUTPUT_2") (pintype "input"))
    )
    (net (code "29") (name "Net-(U3-CFLY+)") (class "Default")
      (node (ref "C7") (pin "2") (pinfunction "2_2") (pintype "unspecified"))
      (node (ref "U3") (pin "6") (pinfunction "CFLY+_6") (pintype "unspecified"))
    )
    (net (code "30") (name "Net-(U3-CFLY-)") (class "Default")
      (node (ref "C7") (pin "1") (pinfunction "1_1") (pintype "unspecified"))
      (node (ref "U3") (pin "3") (pinfunction "CFLY-_3") (pintype "unspecified"))
    )
    (net (code "31") (name "Net-(U3-EN)") (class "Default")
      (node (ref "R3") (pin "2") (pinfunction "2_2") (pintype "input"))
      (node (ref "U3") (pin "5") (pinfunction "EN_5") (pintype "unspecified"))
    )
    (net (code "32") (name "Net-(U6-A)") (class "Default")
      (node (ref "D4") (pin "1") (pinfunction "1_1") (pintype "unspecified"))
      (node (ref "R22") (pin "2") (pinfunction "2_2") (pintype "input"))
      (node (ref "U6") (pin "6") (pinfunction "A_6") (pintype "unspecified"))
    )
    (net (code "33") (name "Net-(U6-B)") (class "Default")
      (node (ref "D4") (pin "2") (pinfunction "2_2") (pintype "unspecified"))
      (node (ref "R20") (pin "2") (pinfunction "2_2") (pintype "input"))
      (node (ref "U6") (pin "7") (pinfunction "B_7") (pintype "unspecified"))
    )
    (net (code "34") (name "Net-(U10-P3.0{slash}RxD{slash}INT4#{slash}T2CLKO)") (class "Default")
      (node (ref "H1") (pin "2") (pinfunction "2_2") (pintype "unspecified"))
      (node (ref "U10") (pin "15") (pinfunction "P3.0/RxD/INT4#/T2CLKO_15") (pintype "input"))
    )
    (net (code "35") (name "Net-(U10-P3.1{slash}TxD{slash}T2)") (class "Default")
      (node (ref "H1") (pin "1") (pinfunction "1_1") (pintype "unspecified"))
      (node (ref "U10") (pin "16") (pinfunction "P3.1/TxD/T2_16") (pintype "input"))
    )
    (net (code "36") (name "Net-(U11A-IN1-)") (class "Default")
      (node (ref "C14") (pin "1") (pinfunction "1_1") (pintype "input"))
      (node (ref "R10") (pin "1") (pinfunction "1_1") (pintype "input"))
      (node (ref "R8") (pin "1") (pinfunction "1_1") (pintype "input"))
      (node (ref "U11") (pin "2") (pinfunction "IN1-_2") (pintype "unspecified"))
    )
    (net (code "37") (name "Net-(U11A-OUT1)") (class "Default")
      (node (ref "C14") (pin "2") (pinfunction "2_2") (pintype "input"))
      (node (ref "R4") (pin "2") (pinfunction "2_2") (pintype "input"))
      (node (ref "R8") (pin "2") (pinfunction "2_2") (pintype "input"))
      (node (ref "U11") (pin "1") (pinfunction "OUT1_1") (pintype "unspecified"))
    )
    (net (code "38") (name "Net-(U11B-IN2-)") (class "Default")
      (node (ref "C16") (pin "2") (pinfunction "2_2") (pintype "input"))
      (node (ref "R10") (pin "2") (pinfunction "2_2") (pintype "input"))
      (node (ref "R10") (pin "3") (pinfunction "3_3") (pintype "input"))
      (node (ref "R11") (pin "2") (pinfunction "2_2") (pintype "input"))
      (node (ref "U11") (pin "6") (pinfunction "IN2-_6") (pintype "unspecified"))
    )
    (net (code "39") (name "Net-(U11B-OUT2)") (class "Default")
      (node (ref "C16") (pin "1") (pinfunction "1_1") (pintype "input"))
      (node (ref "R11") (pin "1") (pinfunction "1_1") (pintype "input"))
      (node (ref "R12") (pin "2") (pinfunction "2_2") (pintype "input"))
      (node (ref "U11") (pin "7") (pinfunction "OUT2_7") (pintype "unspecified"))
    )
    (net (code "40") (name "Net-(U11C-IN3+)") (class "Default")
      (node (ref "R12") (pin "1") (pinfunction "1_1") (pintype "input"))
      (node (ref "R13") (pin "2") (pinfunction "2_2") (pintype "input"))
      (node (ref "U11") (pin "10") (pinfunction "IN3+_10") (pintype "unspecified"))
    )
    (net (code "41") (name "Net-(U11C-IN3-)") (class "Default")
      (node (ref "R4") (pin "1") (pinfunction "1_1") (pintype "input"))
      (node (ref "R5") (pin "2") (pinfunction "2_2") (pintype "input"))
      (node (ref "U11") (pin "9") (pinfunction "IN3-_9") (pintype "unspecified"))
    )
    (net (code "42") (name "Net-(U11D-IN4+)") (class "Default")
      (node (ref "R6") (pin "1") (pinfunction "1_1") (pintype "input"))
      (node (ref "R7") (pin "1") (pinfunction "1_1") (pintype "input"))
      (node (ref "U11") (pin "12") (pinfunction "IN4+_12") (pintype "unspecified"))
    )
    (net (code "43") (name "P12") (class "Default")
      (node (ref "R19") (pin "1") (pinfunction "1_1") (pintype "input"))
      (node (ref "U10") (pin "5") (pinfunction "ECI/SS/ADC2/P1.2_5") (pintype "input"))
      (node (ref "U6") (pin "2") (pinfunction "#RE_2") (pintype "unspecified"))
      (node (ref "U6") (pin "3") (pinfunction "DE_3") (pintype "unspecified"))
    )
    (net (code "44") (name "P20") (class "Default")
      (node (ref "C18") (pin "2") (pinfunction "2_2") (pintype "input"))
      (node (ref "R23") (pin "2") (pinfunction "2_2") (pintype "input"))
      (node (ref "U10") (pin "23") (pinfunction "P2.0/RSTOUT_LOW_23") (pintype "input"))
      (node (ref "U7") (pin "1") (pinfunction "G_1") (pintype "unspecified"))
    )
    (net (code "45") (name "P21") (class "Default")
      (node (ref "CN5") (pin "5") (pinfunction "5_5") (pintype "unspecified"))
      (node (ref "U10") (pin "24") (pinfunction "P2.1/SCLK_2_24") (pintype "input"))
    )
    (net (code "46") (name "P22") (class "Default")
      (node (ref "CN5") (pin "4") (pinfunction "4_4") (pintype "unspecified"))
      (node (ref "U10") (pin "25") (pinfunction "P2.2/MISO_2_25") (pintype "input"))
    )
    (net (code "47") (name "P23") (class "Default")
      (node (ref "CN5") (pin "3") (pinfunction "3_3") (pintype "unspecified"))
      (node (ref "U10") (pin "26") (pinfunction "P2.3/MOSI_2_26") (pintype "input"))
    )
    (net (code "48") (name "P24") (class "Default")
      (node (ref "CN5") (pin "2") (pinfunction "2_2") (pintype "unspecified"))
      (node (ref "U10") (pin "27") (pinfunction "P2.4/ECI_3/SS_2_27") (pintype "input"))
    )
    (net (code "49") (name "P25") (class "Default")
      (node (ref "C17") (pin "2") (pinfunction "2_2") (pintype "input"))
      (node (ref "R17") (pin "2") (pinfunction "2_2") (pintype "input"))
      (node (ref "U10") (pin "28") (pinfunction "P2.5/CCP0_3_28") (pintype "input"))
      (node (ref "U5") (pin "1") (pinfunction "G_1") (pintype "unspecified"))
    )
    (net (code "50") (name "P36") (class "Default")
      (node (ref "R26") (pin "1") (pinfunction "1_1") (pintype "input"))
      (node (ref "U10") (pin "21") (pinfunction "P3.6/INT2#/RxD_2/CCP1_2_21") (pintype "input"))
    )
    (net (code "51") (name "P37") (class "Default")
      (node (ref "R15") (pin "1") (pinfunction "1_1") (pintype "input"))
      (node (ref "U10") (pin "22") (pinfunction "P3.7/INT3#/TxD_2/CCP2/CCP2_2_22") (pintype "input"))
    )
    (net (code "52") (name "SCL") (class "Default")
      (node (ref "U10") (pin "2") (pinfunction "CCP2_3/P2.7_2") (pintype "input"))
    )
    (net (code "53") (name "SDA") (class "Default")
      (node (ref "U10") (pin "1") (pinfunction "CCP1_3/P2.6_1") (pintype "input"))
    )
    (net (code "54") (name "SN+") (class "Default")
      (node (ref "CN4") (pin "2") (pinfunction "2_2") (pintype "unspecified"))
      (node (ref "U11") (pin "3") (pinfunction "IN1+_3") (pintype "unspecified"))
    )
    (net (code "55") (name "SN-") (class "Default")
      (node (ref "CN4") (pin "1") (pinfunction "1_1") (pintype "unspecified"))
      (node (ref "U11") (pin "5") (pinfunction "IN2+_5") (pintype "unspecified"))
    )
    (net (code "56") (name "VBAT") (class "Default")
      (node (ref "C1") (pin "1") (pinfunction "1_1") (pintype "input"))
      (node (ref "CN4") (pin "4") (pinfunction "4_4") (pintype "unspecified"))
      (node (ref "R6") (pin "2") (pinfunction "2_2") (pintype "input"))
      (node (ref "SW1") (pin "2") (pinfunction "2_2") (pintype "unspecified"))
      (node (ref "U1") (pin "1") (pinfunction "VIN_1") (pintype "input"))
    )
    (net (code "57") (name "VCC") (class "Default")
      (node (ref "C11") (pin "2") (pinfunction "2_2") (pintype "unspecified"))
      (node (ref "C12") (pin "2") (pinfunction "2_2") (pintype "input"))
      (node (ref "C15") (pin "1") (pinfunction "1_1") (pintype "input"))
      (node (ref "C17") (pin "1") (pinfunction "1_1") (pintype "input"))
      (node (ref "C18") (pin "1") (pinfunction "1_1") (pintype "input"))
      (node (ref "C2") (pin "2") (pinfunction "2_2") (pintype "input"))
      (node (ref "C20") (pin "2") (pinfunction "2_2") (pintype "input"))
      (node (ref "C23") (pin "2") (pinfunction "2_2") (pintype "input"))
      (node (ref "C3") (pin "2") (pinfunction "2_2") (pintype "input"))
      (node (ref "C4") (pin "1") (pinfunction "1_1") (pintype "input"))
      (node (ref "CN5") (pin "7") (pinfunction "7_7") (pintype "unspecified"))
      (node (ref "D1") (pin "1") (pinfunction "C_1") (pintype "unspecified"))
      (node (ref "H1") (pin "3") (pinfunction "3_3") (pintype "unspecified"))
      (node (ref "L1") (pin "1") (pinfunction "1_1") (pintype "unspecified"))
      (node (ref "LED1") (pin "1") (pinfunction "C_1") (pintype "input"))
      (node (ref "R17") (pin "1") (pinfunction "1_1") (pintype "input"))
      (node (ref "R18") (pin "2") (pinfunction "2_2") (pintype "input"))
      (node (ref "R21") (pin "2") (pinfunction "2_2") (pintype "input"))
      (node (ref "R23") (pin "1") (pinfunction "1_1") (pintype "input"))
      (node (ref "R3") (pin "1") (pinfunction "1_1") (pintype "input"))
      (node (ref "U1") (pin "4") (pinfunction "FEEDBACK_4") (pintype "input"))
      (node (ref "U10") (pin "12") (pinfunction "Vcc_12") (pintype "input"))
      (node (ref "U11") (pin "4") (pinfunction "VCC+_4") (pintype "unspecified"))
      (node (ref "U3") (pin "2") (pinfunction "IN_2") (pintype "unspecified"))
      (node (ref "U4") (pin "1") (pinfunction "1_1") (pintype "input"))
      (node (ref "U5") (pin "2") (pinfunction "S_2") (pintype "unspecified"))
      (node (ref "U6") (pin "8") (pinfunction "VCC_8") (pintype "unspecified"))
      (node (ref "U7") (pin "2") (pinfunction "S_2") (pintype "unspecified"))
      (node (ref "U8") (pin "1") (pinfunction "1_1") (pintype "input"))
    )
    (net (code "58") (name "VEE") (class "Default")
      (node (ref "C13") (pin "2") (pinfunction "2_2") (pintype "input"))
      (node (ref "C8") (pin "2") (pinfunction "2_2") (pintype "unspecified"))
      (node (ref "U11") (pin "11") (pinfunction "VCC-_11") (pintype "unspecified"))
      (node (ref "U3") (pin "1") (pinfunction "OUT_1") (pintype "unspecified"))
    )
    (net (code "59") (name "VRM") (class "Default")
      (node (ref "D3") (pin "1") (pinfunction "C_1") (pintype "unspecified"))
      (node (ref "D5") (pin "1") (pinfunction "C_1") (pintype "unspecified"))
      (node (ref "R14") (pin "1") (pinfunction "1_1") (pintype "input"))
      (node (ref "R24") (pin "2") (pinfunction "2_2") (pintype "input"))
      (node (ref "R25") (pin "1") (pinfunction "1_1") (pintype "input"))
      (node (ref "R9") (pin "2") (pinfunction "2_2") (pintype "input"))
      (node (ref "RELAY1") (pin "2") (pinfunction "2_2") (pintype "input"))
      (node (ref "RELAY2") (pin "2") (pinfunction "2_2") (pintype "input"))
    )
    (net (code "60") (name "XTAL1") (class "Default")
      (node (ref "C19") (pin "1") (pinfunction "1_1") (pintype "input"))
      (node (ref "U10") (pin "10") (pinfunction "XTAL1/TxD_3/ADC7/P1.7_10") (pintype "input"))
      (node (ref "X1") (pin "2") (pinfunction "2_2") (pintype "unspecified"))
    )
    (net (code "61") (name "XTAL2") (class "Default")
      (node (ref "C22") (pin "1") (pinfunction "1_1") (pintype "input"))
      (node (ref "U10") (pin "9") (pinfunction "XTAL2/RxD_3/ADC6/P1.6_9") (pintype "input"))
      (node (ref "X1") (pin "1") (pinfunction "1_1") (pintype "unspecified"))
    )
    (net (code "62") (name "unconnected-(C5-Pad1)") (class "Default")
      (node (ref "C5") (pin "1") (pinfunction "1_1") (pintype "unspecified"))
    )
    (net (code "63") (name "unconnected-(C5-Pad2)") (class "Default")
      (node (ref "C5") (pin "2") (pinfunction "2_2") (pintype "unspecified"))
    )
    (net (code "64") (name "unconnected-(C6-Pad1)") (class "Default")
      (node (ref "C6") (pin "1") (pinfunction "1_1") (pintype "unspecified"))
    )
    (net (code "65") (name "unconnected-(C6-Pad2)") (class "Default")
      (node (ref "C6") (pin "2") (pinfunction "2_2") (pintype "unspecified"))
    )
    (net (code "66") (name "unconnected-(C9-Pad1)") (class "Default")
      (node (ref "C9") (pin "1") (pinfunction "1_1") (pintype "unspecified"))
    )
    (net (code "67") (name "unconnected-(C9-Pad2)") (class "Default")
      (node (ref "C9") (pin "2") (pinfunction "2_2") (pintype "unspecified"))
    )
    (net (code "68") (name "unconnected-(C10-Pad1)") (class "Default")
      (node (ref "C10") (pin "1") (pinfunction "1_1") (pintype "input"))
    )
    (net (code "69") (name "unconnected-(C10-Pad2)") (class "Default")
      (node (ref "C10") (pin "2") (pinfunction "2_2") (pintype "input"))
    )
    (net (code "70") (name "unconnected-(C21-Pad1)") (class "Default")
      (node (ref "C21") (pin "1") (pinfunction "1_1") (pintype "input"))
    )
    (net (code "71") (name "unconnected-(C21-Pad2)") (class "Default")
      (node (ref "C21") (pin "2") (pinfunction "2_2") (pintype "input"))
    )
    (net (code "72") (name "unconnected-(R2-Pad1)") (class "Default")
      (node (ref "R2") (pin "1") (pinfunction "1_1") (pintype "input"))
    )
    (net (code "73") (name "unconnected-(R2-Pad2)") (class "Default")
      (node (ref "R2") (pin "2") (pinfunction "2_2") (pintype "input"))
    )
    (net (code "74") (name "unconnected-(R28-Pad1)") (class "Default")
      (node (ref "R28") (pin "1") (pinfunction "1_1") (pintype "input"))
    )
    (net (code "75") (name "unconnected-(R28-Pad2)") (class "Default")
      (node (ref "R28") (pin "2") (pinfunction "2_2") (pintype "input"))
    )
    (net (code "76") (name "unconnected-(R29-Pad1)") (class "Default")
      (node (ref "R29") (pin "1") (pinfunction "1_1") (pintype "input"))
    )
    (net (code "77") (name "unconnected-(R29-Pad2)") (class "Default")
      (node (ref "R29") (pin "2") (pinfunction "2_2") (pintype "input"))
    )
    (net (code "78") (name "unconnected-(SW1-Pad3)") (class "Default")
      (node (ref "SW1") (pin "3") (pinfunction "3_3") (pintype "unspecified+no_connect"))
    )
    (net (code "79") (name "unconnected-(SW1-Pad4)") (class "Default")
      (node (ref "SW1") (pin "4") (pinfunction "4_4") (pintype "unspecified+no_connect"))
    )
    (net (code "80") (name "unconnected-(SW1-Pad5)") (class "Default")
      (node (ref "SW1") (pin "5") (pinfunction "5_5") (pintype "unspecified+no_connect"))
    )
    (net (code "81") (name "unconnected-(U9-A0-Pad1)") (class "Default")
      (node (ref "U9") (pin "1") (pinfunction "A0_1") (pintype "unspecified"))
    )
    (net (code "82") (name "unconnected-(U9-A1-Pad2)") (class "Default")
      (node (ref "U9") (pin "2") (pinfunction "A1_2") (pintype "unspecified"))
    )
    (net (code "83") (name "unconnected-(U9-A2-Pad3)") (class "Default")
      (node (ref "U9") (pin "3") (pinfunction "A2_3") (pintype "unspecified"))
    )
    (net (code "84") (name "unconnected-(U9-GND-Pad4)") (class "Default")
      (node (ref "U9") (pin "4") (pinfunction "GND_4") (pintype "unspecified"))
    )
    (net (code "85") (name "unconnected-(U9-SCL-Pad6)") (class "Default")
      (node (ref "U9") (pin "6") (pinfunction "SCL_6") (pintype "unspecified"))
    )
    (net (code "86") (name "unconnected-(U9-SDA-Pad5)") (class "Default")
      (node (ref "U9") (pin "5") (pinfunction "SDA_5") (pintype "unspecified"))
    )
    (net (code "87") (name "unconnected-(U9-VCC-Pad8)") (class "Default")
      (node (ref "U9") (pin "8") (pinfunction "VCC_8") (pintype "unspecified"))
    )
    (net (code "88") (name "unconnected-(U9-WP-Pad7)") (class "Default")
      (node (ref "U9") (pin "7") (pinfunction "WP_7") (pintype "unspecified"))
    )
    (net (code "89") (name "unconnected-(U10-MCLKO{slash}RST{slash}P5.4-Pad11)") (class "Default")
      (node (ref "U10") (pin "11") (pinfunction "MCLKO/RST/P5.4_11") (pintype "input+no_connect"))
    )
    (net (code "90") (name "unconnected-(U10-P3.2{slash}INT0-Pad17)") (class "Default")
      (node (ref "U10") (pin "17") (pinfunction "P3.2/INT0_17") (pintype "input+no_connect"))
    )
    (net (code "91") (name "unconnected-(U10-P3.3{slash}INT1-Pad18)") (class "Default")
      (node (ref "U10") (pin "18") (pinfunction "P3.3/INT1_18") (pintype "input+no_connect"))
    )
    (net (code "92") (name "unconnected-(U10-P3.4{slash}T0{slash}T1CLKO{slash}ECI_2-Pad19)") (class "Default")
      (node (ref "U10") (pin "19") (pinfunction "P3.4/T0/T1CLKO/ECI_2_19") (pintype "input+no_connect"))
    )
    (net (code "93") (name "unconnected-(U10-P3.5{slash}T1{slash}T0CLKO{slash}CCP0_2-Pad20)") (class "Default")
      (node (ref "U10") (pin "20") (pinfunction "P3.5/T1/T0CLKO/CCP0_2_20") (pintype "input+no_connect"))
    )
    (net (code "94") (name "unconnected-(U10-P5.5-Pad13)") (class "Default")
      (node (ref "U10") (pin "13") (pinfunction "P5.5_13") (pintype "input+no_connect"))
    )
    (net (code "95") (name "unconnected-(U10-SCLK{slash}ADC5{slash}P1.5-Pad8)") (class "Default")
      (node (ref "U10") (pin "8") (pinfunction "SCLK/ADC5/P1.5_8") (pintype "input+no_connect"))
    )
  )
)
